# Main-v4_0.net
KiCad netlist of a schematic drawn in EAGLE
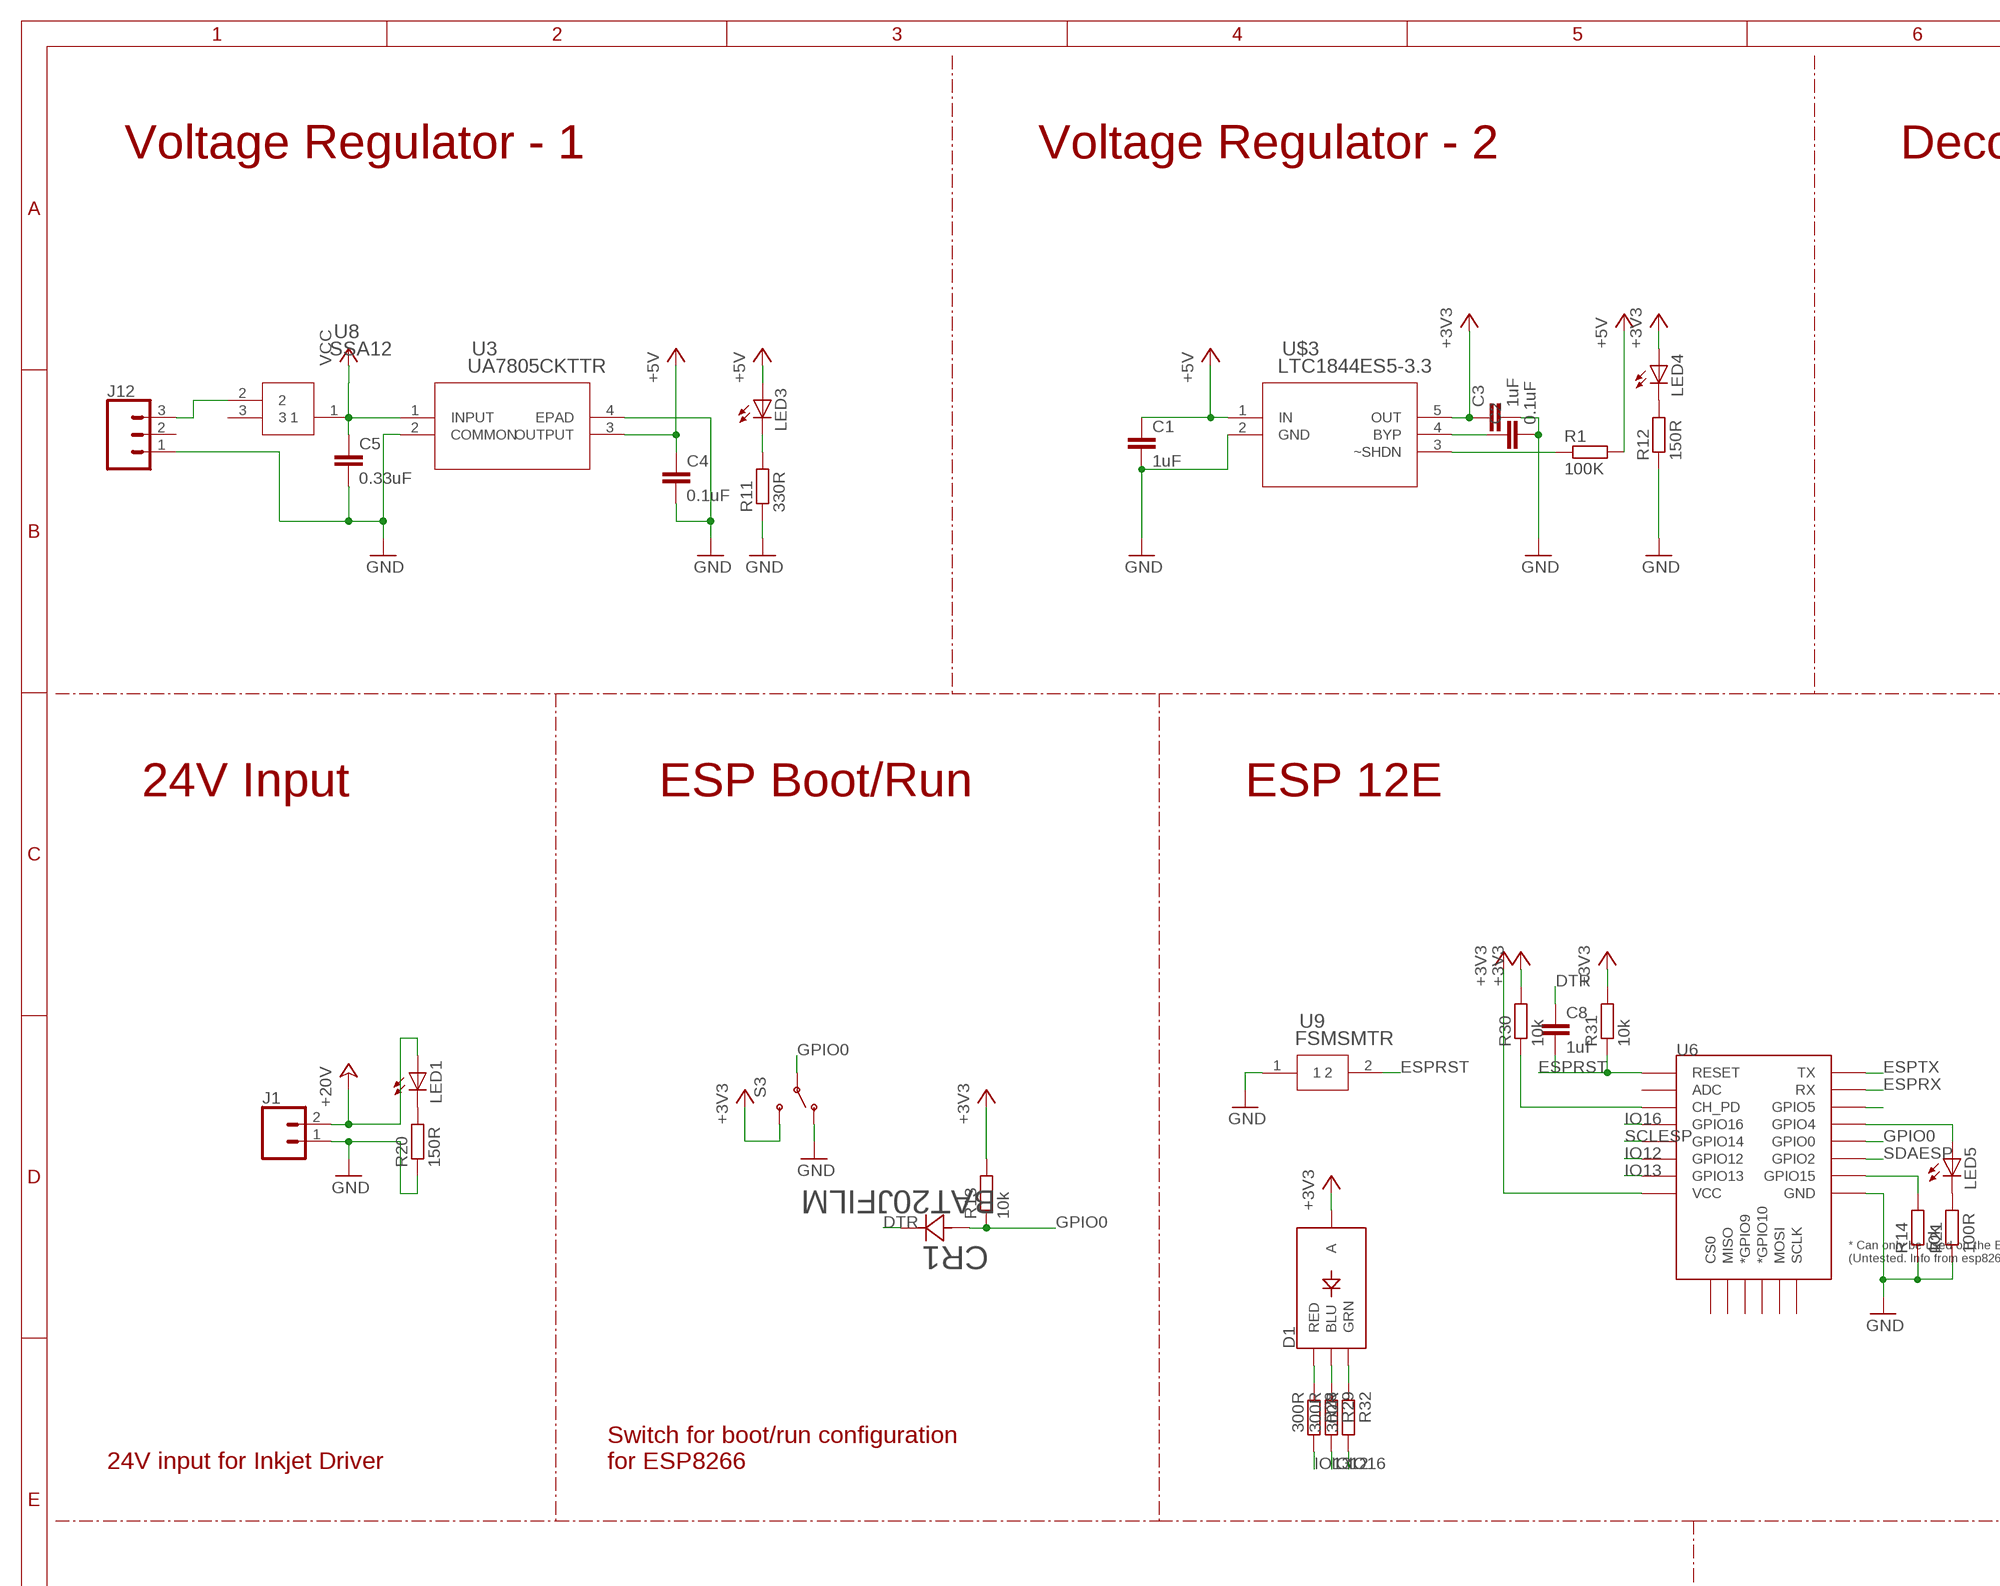
[diagram p0: schematic, sheet 1, part 1 of 3]
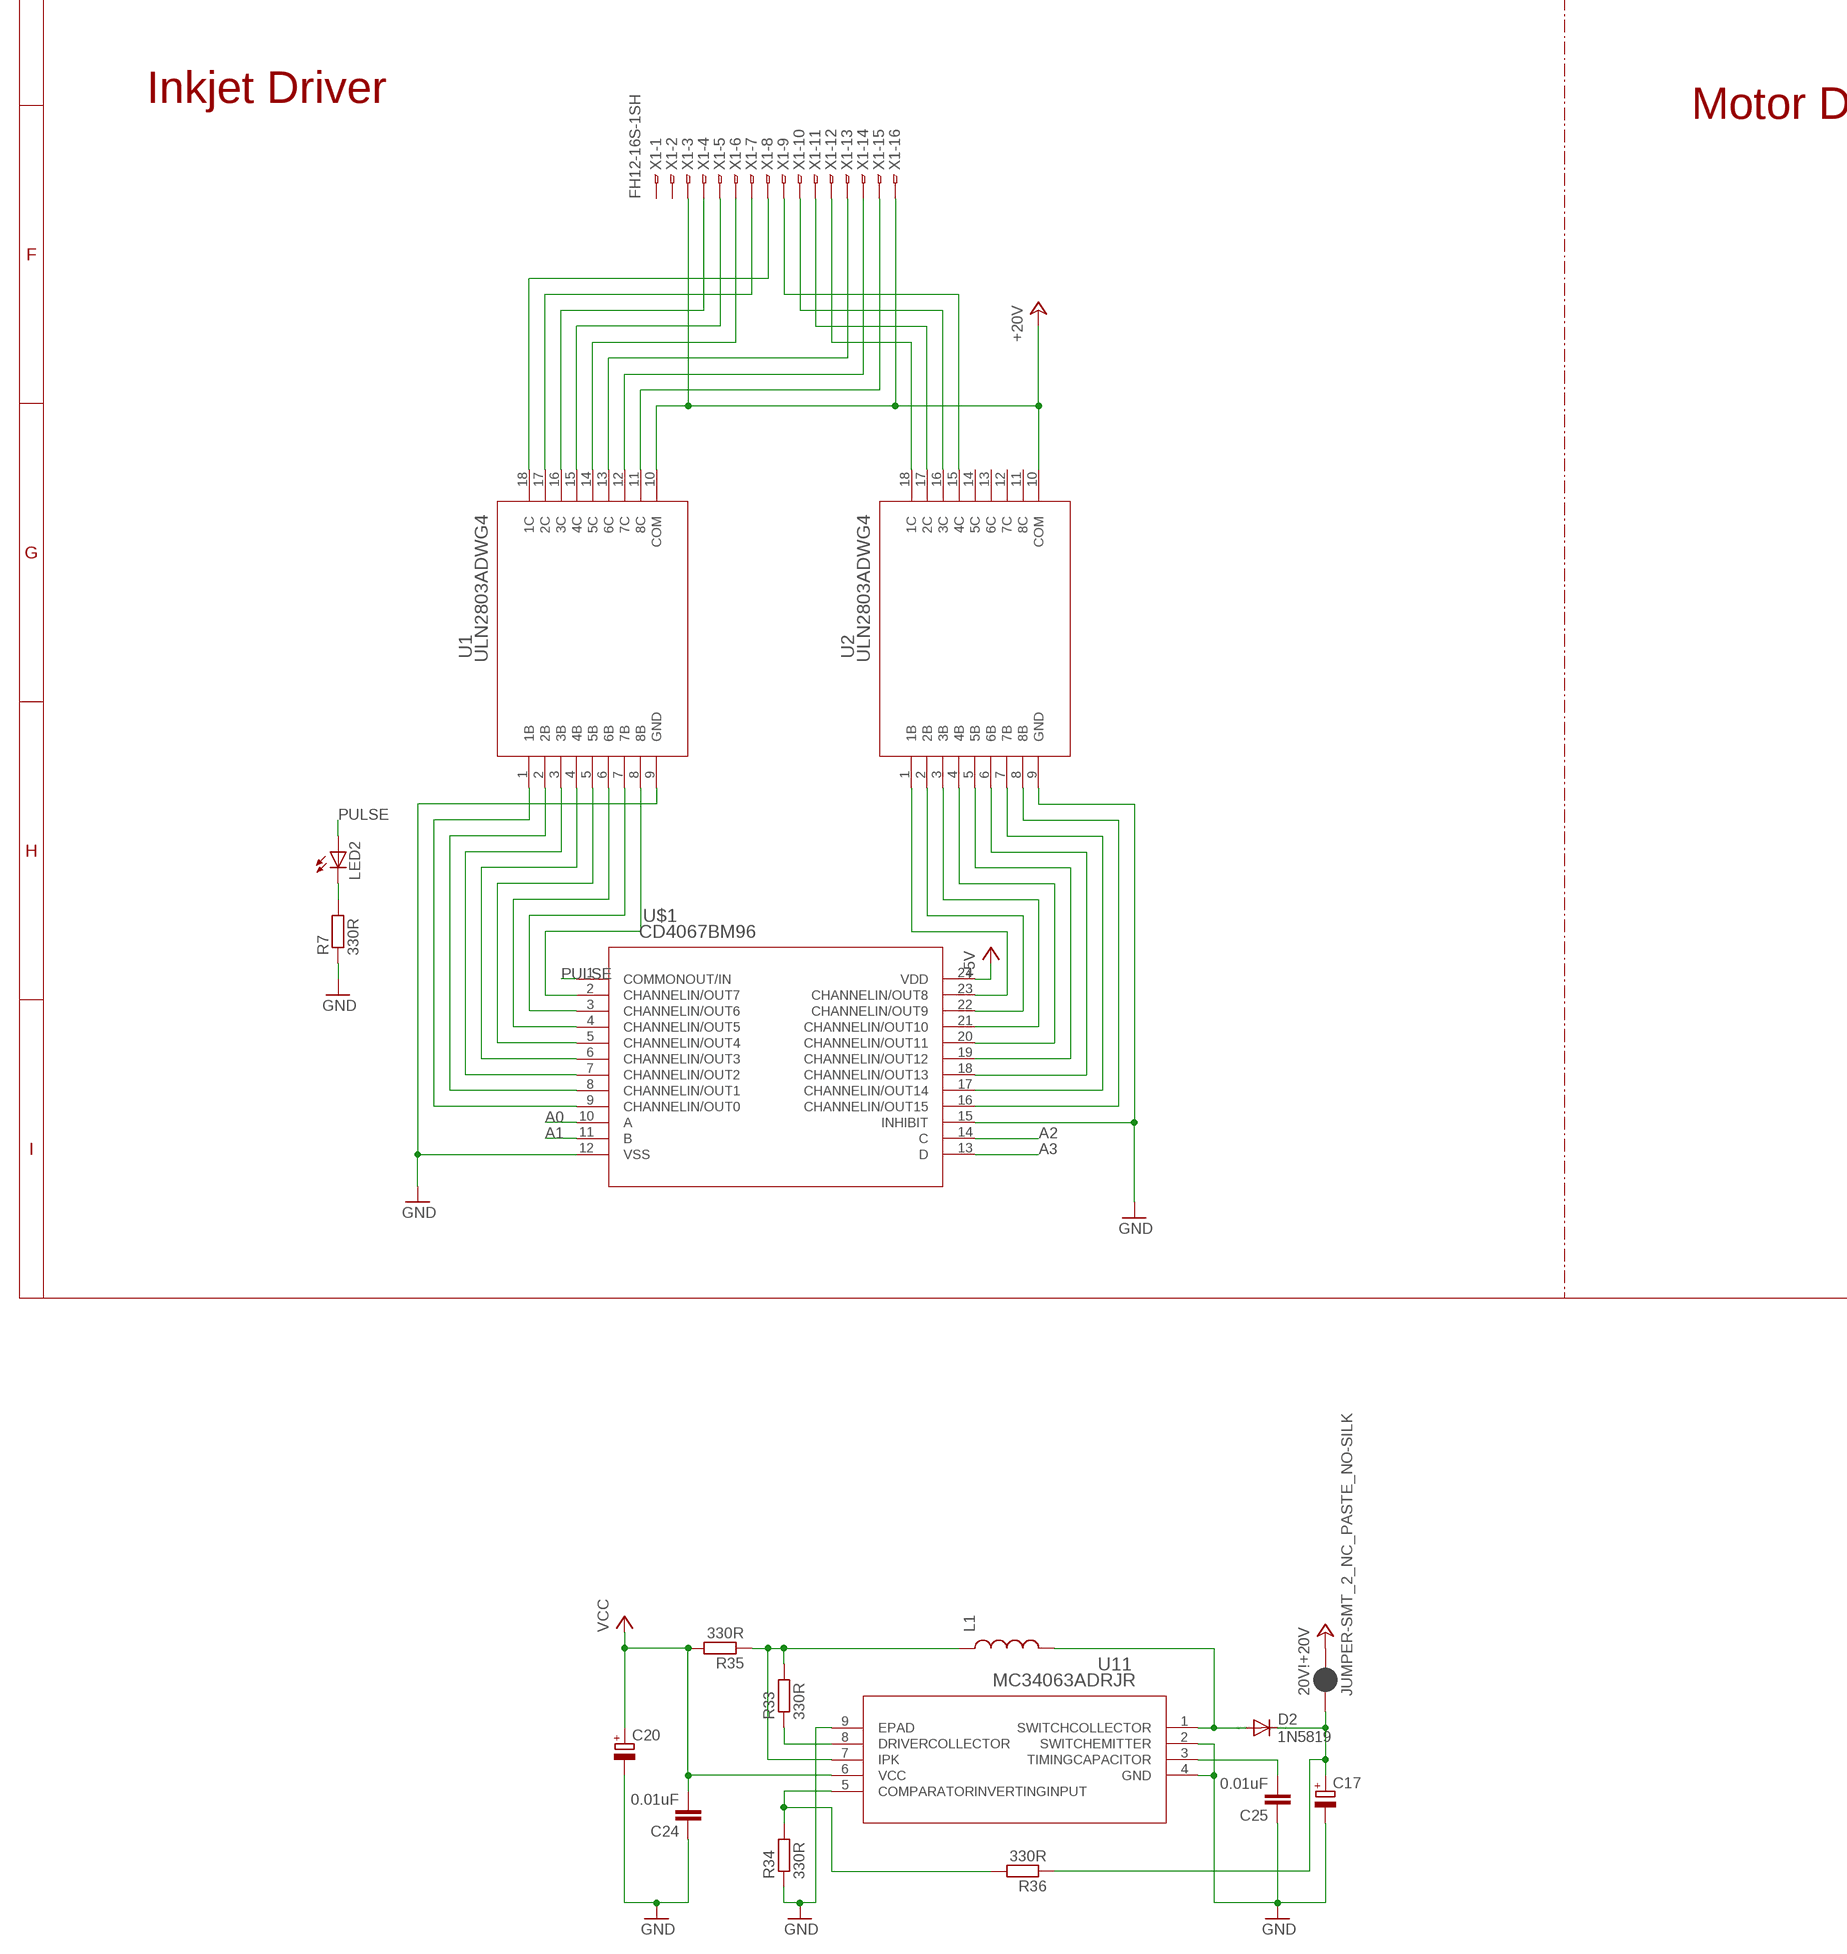
[diagram p1: schematic, sheet 1, part 2 of 3]
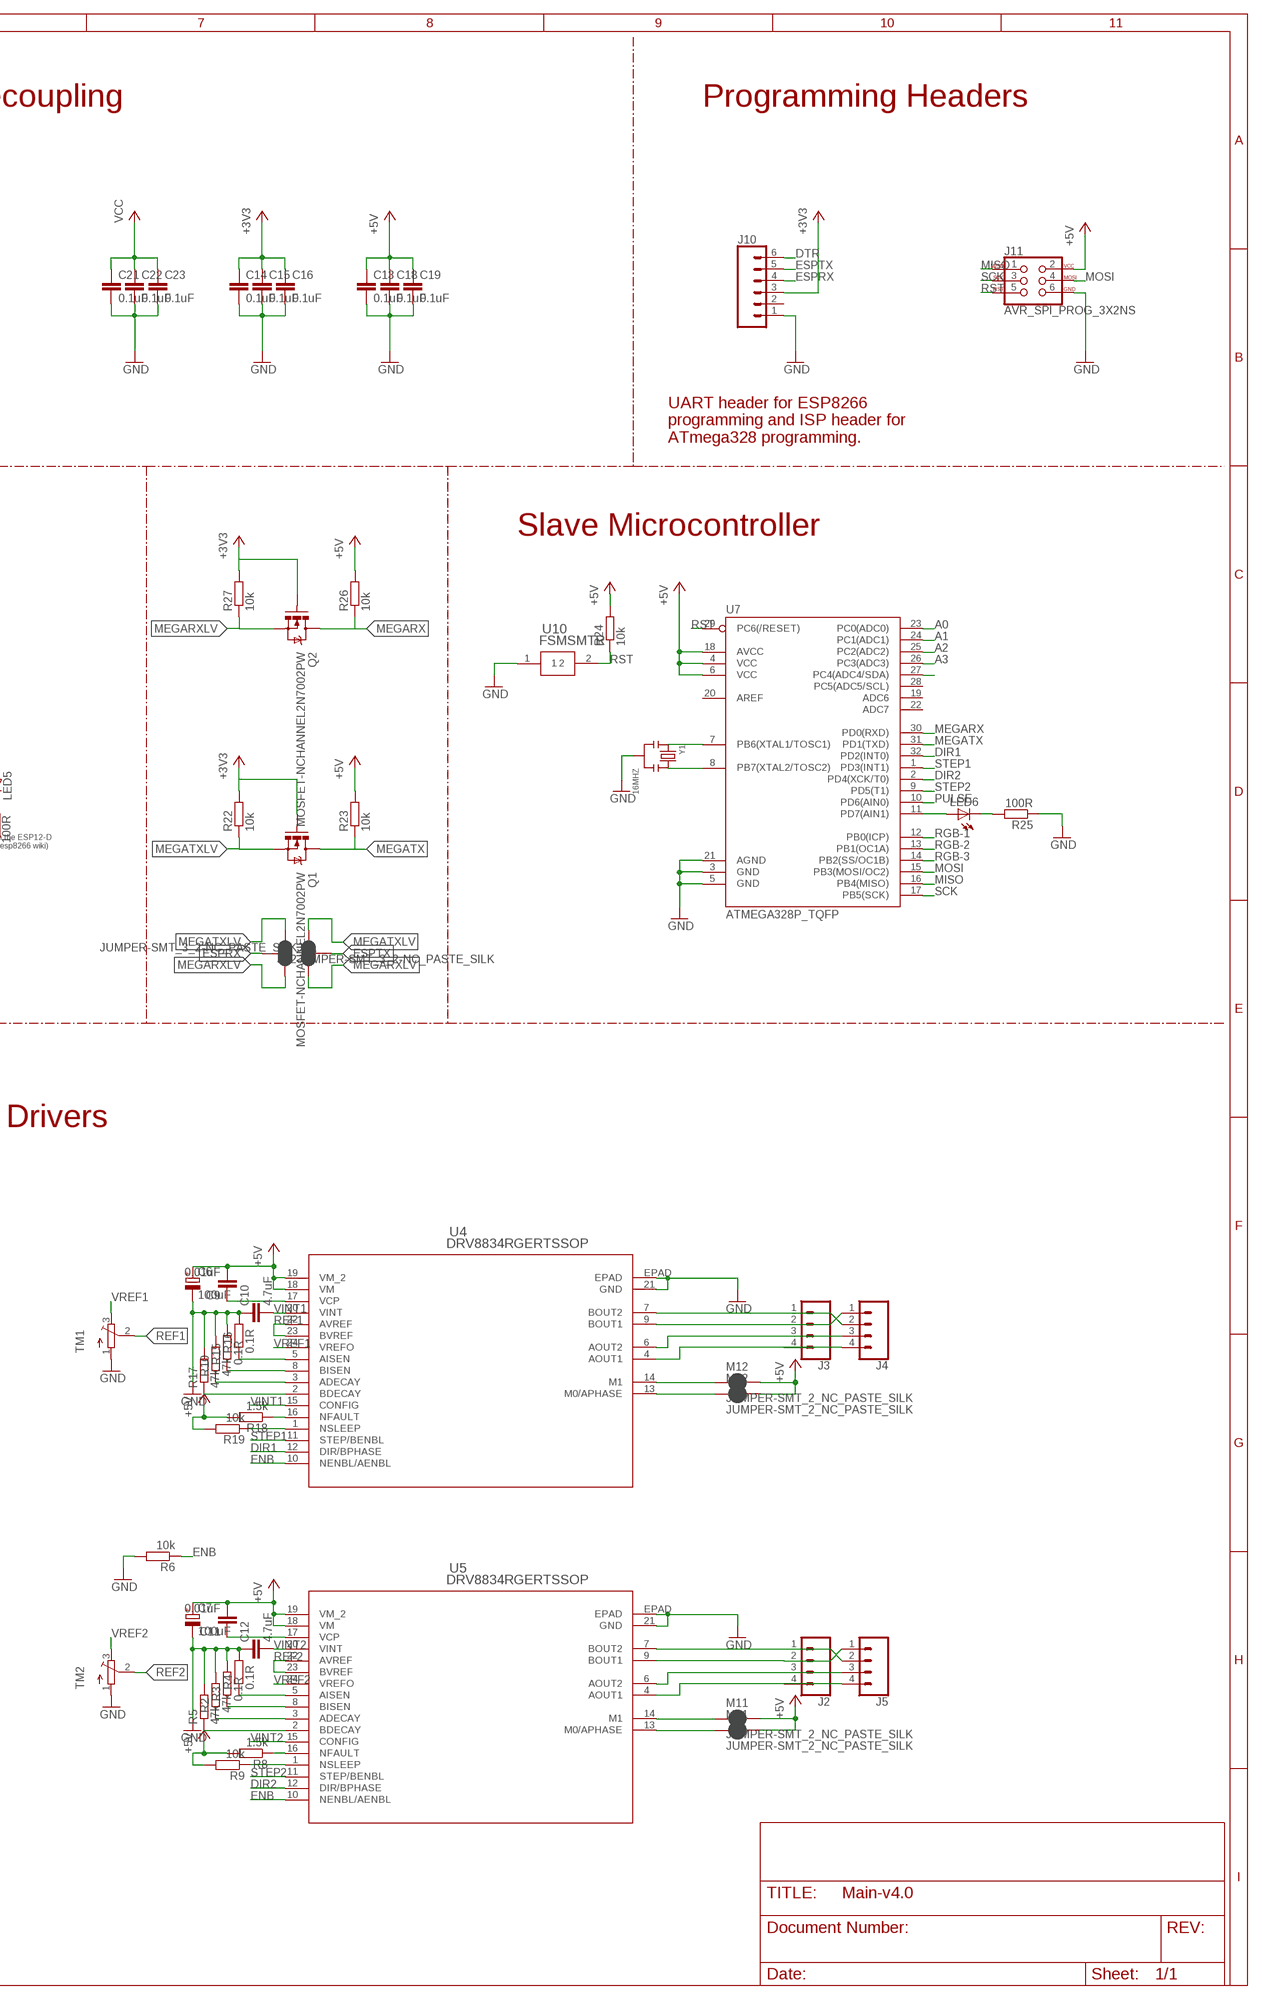
[diagram p2: schematic, sheet 1, part 3 of 3]

(export (version "E")
  (design (tool "Eeschema 10.0.6"))
  (components
    (comp (ref "20V!")
      (value "JUMPER-SMT_2_NC_PASTE_NO-SILK")
      (footprint "eagle-import:SMT-JUMPER_2_NC_PASTE_NO-SILK")
      (libsource (lib "eagle-import") (part "JUMPER-SMT_2_NC_PASTE_NO-SILK"))
    )
    (comp (ref "C1")
      (value "1uF")
      (footprint "eagle-import:C0603")
      (libsource (lib "eagle-import") (part "C-EUC0603"))
    )
    (comp (ref "C2")
      (value "0.1uF")
      (footprint "eagle-import:C0603")
      (libsource (lib "eagle-import") (part "C-EUC0603"))
    )
    (comp (ref "C3")
      (value "1uF")
      (footprint "eagle-import:C0603")
      (libsource (lib "eagle-import") (part "C-EUC0603"))
    )
    (comp (ref "C4")
      (value "0.1uF")
      (footprint "eagle-import:C0603")
      (libsource (lib "eagle-import") (part "C-EUC0603"))
    )
    (comp (ref "C5")
      (value "0.33uF")
      (footprint "eagle-import:C0603")
      (libsource (lib "eagle-import") (part "C-EUC0603"))
    )
    (comp (ref "C6")
      (value "100uF")
      (footprint "eagle-import:E5-5")
      (libsource (lib "eagle-import") (part "CPOL-EUE5-5"))
    )
    (comp (ref "C7")
      (value "100uF")
      (footprint "eagle-import:E5-5")
      (libsource (lib "eagle-import") (part "CPOL-EUE5-5"))
    )
    (comp (ref "C8")
      (value "1uf")
      (footprint "eagle-import:C0603")
      (libsource (lib "eagle-import") (part "resistor_348_C-EUC0603"))
    )
    (comp (ref "C9")
      (value "0.01uF")
      (footprint "eagle-import:C0603K")
      (libsource (lib "eagle-import") (part "resistor_348_C-EUC0603K"))
    )
    (comp (ref "C10")
      (value "4.7uF")
      (footprint "eagle-import:C0603K")
      (libsource (lib "eagle-import") (part "resistor_348_C-EUC0603K"))
    )
    (comp (ref "C11")
      (value "0.01uF")
      (footprint "eagle-import:C0603K")
      (libsource (lib "eagle-import") (part "resistor_348_C-EUC0603K"))
    )
    (comp (ref "C12")
      (value "4.7uF")
      (footprint "eagle-import:C0603K")
      (libsource (lib "eagle-import") (part "resistor_348_C-EUC0603K"))
    )
    (comp (ref "C13")
      (value "0.1uF")
      (footprint "eagle-import:C0603")
      (libsource (lib "eagle-import") (part "C-EUC0603"))
    )
    (comp (ref "C14")
      (value "0.1uF")
      (footprint "eagle-import:C0603")
      (libsource (lib "eagle-import") (part "C-EUC0603"))
    )
    (comp (ref "C15")
      (value "0.1uF")
      (footprint "eagle-import:C0603")
      (libsource (lib "eagle-import") (part "C-EUC0603"))
    )
    (comp (ref "C16")
      (value "0.1uF")
      (footprint "eagle-import:C0603")
      (libsource (lib "eagle-import") (part "C-EUC0603"))
    )
    (comp (ref "C17")
      (value "CPOL-EU153CLV-1010")
      (footprint "eagle-import:153CLV-1010")
      (libsource (lib "eagle-import") (part "resistor_348_CPOL-EU153CLV-1010"))
    )
    (comp (ref "C18")
      (value "0.1uF")
      (footprint "eagle-import:C0603")
      (libsource (lib "eagle-import") (part "C-EUC0603"))
    )
    (comp (ref "C19")
      (value "0.1uF")
      (footprint "eagle-import:C0603")
      (libsource (lib "eagle-import") (part "C-EUC0603"))
    )
    (comp (ref "C20")
      (value "CPOL-EUSMCC")
      (footprint "eagle-import:SMC_C")
      (libsource (lib "eagle-import") (part "resistor_348_CPOL-EUSMCC"))
    )
    (comp (ref "C21")
      (value "0.1uF")
      (footprint "eagle-import:C0603")
      (libsource (lib "eagle-import") (part "C-EUC0603"))
    )
    (comp (ref "C22")
      (value "0.1uF")
      (footprint "eagle-import:C0603")
      (libsource (lib "eagle-import") (part "C-EUC0603"))
    )
    (comp (ref "C23")
      (value "0.1uF")
      (footprint "eagle-import:C0603")
      (libsource (lib "eagle-import") (part "C-EUC0603"))
    )
    (comp (ref "C24")
      (value "0.01uF")
      (footprint "eagle-import:C0603K")
      (libsource (lib "eagle-import") (part "resistor_348_C-EUC0603K"))
    )
    (comp (ref "C25")
      (value "0.01uF")
      (footprint "eagle-import:C0603K")
      (libsource (lib "eagle-import") (part "resistor_348_C-EUC0603K"))
    )
    (comp (ref "CR1")
      (value "BAT20JFILM")
      (footprint "eagle-import:SOD-323")
      (libsource (lib "eagle-import") (part "BAT20JFILM"))
    )
    (comp (ref "D1")
      (value "LED-RGB-CASMD")
      (footprint "eagle-import:LED-TRICOLOR-SMD")
      (libsource (lib "eagle-import") (part "LED-RGB-CASMD"))
    )
    (comp (ref "D2")
      (value "1N5819")
      (footprint "eagle-import:SOD123")
      (libsource (lib "eagle-import") (part "1N5819"))
    )
    (comp (ref "J1")
      (value "CONN_02")
      (footprint "eagle-import:1X02")
      (libsource (lib "eagle-import") (part "CONN_02"))
    )
    (comp (ref "J2")
      (value "CONN_04")
      (footprint "eagle-import:1X04")
      (libsource (lib "eagle-import") (part "CONN_04"))
    )
    (comp (ref "J3")
      (value "CONN_04")
      (footprint "eagle-import:1X04")
      (libsource (lib "eagle-import") (part "CONN_04"))
    )
    (comp (ref "J4")
      (value "CONN_04")
      (footprint "eagle-import:1X04")
      (libsource (lib "eagle-import") (part "CONN_04"))
    )
    (comp (ref "J5")
      (value "CONN_04")
      (footprint "eagle-import:1X04")
      (libsource (lib "eagle-import") (part "CONN_04"))
    )
    (comp (ref "J10")
      (value "CONN_06NO_SILK_NO_POP")
      (footprint "eagle-import:1X06_NO_SILK")
      (libsource (lib "eagle-import") (part "CONN_06NO_SILK_NO_POP"))
    )
    (comp (ref "J11")
      (value "AVR_SPI_PROG_3X2NS")
      (footprint "eagle-import:2X3-NS")
      (libsource (lib "eagle-import") (part "AVR_SPI_PROG_3X2NS"))
    )
    (comp (ref "J12")
      (value "CONN_03")
      (footprint "eagle-import:1X03")
      (libsource (lib "eagle-import") (part "CONN_03"))
    )
    (comp (ref "JP1")
      (value "JUMPER-SMT_3_2-NC_PASTE_SILK")
      (footprint "eagle-import:SMT-JUMPER_3_2-NC_PASTE_SILK")
      (libsource (lib "eagle-import") (part "JUMPER-SMT_3_2-NC_PASTE_SILK"))
    )
    (comp (ref "JP2")
      (value "JUMPER-SMT_3_2-NC_PASTE_SILK")
      (footprint "eagle-import:SMT-JUMPER_3_2-NC_PASTE_SILK")
      (libsource (lib "eagle-import") (part "JUMPER-SMT_3_2-NC_PASTE_SILK"))
    )
    (comp (ref "L1")
      (value "INDUCTORCR54")
      (footprint "eagle-import:CR54")
      (libsource (lib "eagle-import") (part "INDUCTORCR54"))
    )
    (comp (ref "LED1")
      (value "LEDSML0603")
      (footprint "eagle-import:SML0603")
      (libsource (lib "eagle-import") (part "LEDSML0603"))
    )
    (comp (ref "LED2")
      (value "LEDSML0603")
      (footprint "eagle-import:SML0603")
      (libsource (lib "eagle-import") (part "LEDSML0603"))
    )
    (comp (ref "LED3")
      (value "LEDSML0603")
      (footprint "eagle-import:SML0603")
      (libsource (lib "eagle-import") (part "LEDSML0603"))
    )
    (comp (ref "LED4")
      (value "LEDSML0603")
      (footprint "eagle-import:SML0603")
      (libsource (lib "eagle-import") (part "LEDSML0603"))
    )
    (comp (ref "LED5")
      (value "LEDSML0603")
      (footprint "eagle-import:SML0603")
      (libsource (lib "eagle-import") (part "LEDSML0603"))
    )
    (comp (ref "LED6")
      (value "LEDSML0603")
      (footprint "eagle-import:SML0603")
      (libsource (lib "eagle-import") (part "LEDSML0603"))
    )
    (comp (ref "M01")
      (value "JUMPER-SMT_2_NC_PASTE_SILK")
      (footprint "eagle-import:SMT-JUMPER_2_NC_PASTE_SILK")
      (libsource (lib "eagle-import") (part "JUMPER-SMT_2_NC_PASTE_SILK"))
    )
    (comp (ref "M02")
      (value "JUMPER-SMT_2_NC_PASTE_SILK")
      (footprint "eagle-import:SMT-JUMPER_2_NC_PASTE_SILK")
      (libsource (lib "eagle-import") (part "JUMPER-SMT_2_NC_PASTE_SILK"))
    )
    (comp (ref "M11")
      (value "JUMPER-SMT_2_NC_PASTE_SILK")
      (footprint "eagle-import:SMT-JUMPER_2_NC_PASTE_SILK")
      (libsource (lib "eagle-import") (part "JUMPER-SMT_2_NC_PASTE_SILK"))
    )
    (comp (ref "M12")
      (value "JUMPER-SMT_2_NC_PASTE_SILK")
      (footprint "eagle-import:SMT-JUMPER_2_NC_PASTE_SILK")
      (libsource (lib "eagle-import") (part "JUMPER-SMT_2_NC_PASTE_SILK"))
    )
    (comp (ref "Q1")
      (value "MOSFET-NCHANNEL2N7002PW")
      (footprint "eagle-import:SOT323")
      (libsource (lib "eagle-import") (part "MOSFET-NCHANNEL2N7002PW"))
    )
    (comp (ref "Q2")
      (value "MOSFET-NCHANNEL2N7002PW")
      (footprint "eagle-import:SOT323")
      (libsource (lib "eagle-import") (part "MOSFET-NCHANNEL2N7002PW"))
    )
    (comp (ref "R1")
      (value "100K")
      (footprint "eagle-import:R0603")
      (libsource (lib "eagle-import") (part "R-EU_R0603"))
    )
    (comp (ref "R2")
      (value "47k")
      (footprint "eagle-import:R0402")
      (libsource (lib "eagle-import") (part "resistor_348_R-EU_R0402"))
    )
    (comp (ref "R3")
      (value "0.1R")
      (footprint "eagle-import:R0402")
      (libsource (lib "eagle-import") (part "resistor_348_R-EU_R0402"))
    )
    (comp (ref "R4")
      (value "0.1R")
      (footprint "eagle-import:R0402")
      (libsource (lib "eagle-import") (part "resistor_348_R-EU_R0402"))
    )
    (comp (ref "R5")
      (value "47k")
      (footprint "eagle-import:R0402")
      (libsource (lib "eagle-import") (part "resistor_348_R-EU_R0402"))
    )
    (comp (ref "R6")
      (value "10k")
      (footprint "eagle-import:R0402")
      (libsource (lib "eagle-import") (part "resistor_348_R-EU_R0402"))
    )
    (comp (ref "R7")
      (value "330R")
      (footprint "eagle-import:R0603")
      (libsource (lib "eagle-import") (part "R-EU_R0603"))
    )
    (comp (ref "R8")
      (value "1.5k")
      (footprint "eagle-import:R0402")
      (libsource (lib "eagle-import") (part "resistor_348_R-EU_R0402"))
    )
    (comp (ref "R9")
      (value "10k")
      (footprint "eagle-import:R0402")
      (libsource (lib "eagle-import") (part "resistor_348_R-EU_R0402"))
    )
    (comp (ref "R10")
      (value "47k")
      (footprint "eagle-import:R0402")
      (libsource (lib "eagle-import") (part "resistor_348_R-EU_R0402"))
    )
    (comp (ref "R11")
      (value "330R")
      (footprint "eagle-import:R0603")
      (libsource (lib "eagle-import") (part "R-EU_R0603"))
    )
    (comp (ref "R12")
      (value "150R")
      (footprint "eagle-import:R0603")
      (libsource (lib "eagle-import") (part "R-EU_R0603"))
    )
    (comp (ref "R13")
      (value "10k")
      (footprint "eagle-import:R0603")
      (libsource (lib "eagle-import") (part "R-EU_R0603"))
    )
    (comp (ref "R14")
      (value "10k")
      (footprint "eagle-import:R0603")
      (libsource (lib "eagle-import") (part "R-EU_R0603"))
    )
    (comp (ref "R15")
      (value "0.1R")
      (footprint "eagle-import:R0402")
      (libsource (lib "eagle-import") (part "resistor_348_R-EU_R0402"))
    )
    (comp (ref "R16")
      (value "0.1R")
      (footprint "eagle-import:R0402")
      (libsource (lib "eagle-import") (part "resistor_348_R-EU_R0402"))
    )
    (comp (ref "R17")
      (value "47k")
      (footprint "eagle-import:R0402")
      (libsource (lib "eagle-import") (part "resistor_348_R-EU_R0402"))
    )
    (comp (ref "R18")
      (value "1.5k")
      (footprint "eagle-import:R0402")
      (libsource (lib "eagle-import") (part "resistor_348_R-EU_R0402"))
    )
    (comp (ref "R19")
      (value "10k")
      (footprint "eagle-import:R0402")
      (libsource (lib "eagle-import") (part "resistor_348_R-EU_R0402"))
    )
    (comp (ref "R20")
      (value "150R")
      (footprint "eagle-import:R0603")
      (libsource (lib "eagle-import") (part "R-EU_R0603"))
    )
    (comp (ref "R21")
      (value "100R")
      (footprint "eagle-import:R0603")
      (libsource (lib "eagle-import") (part "R-EU_R0603"))
    )
    (comp (ref "R22")
      (value "10k")
      (footprint "eagle-import:R0603")
      (libsource (lib "eagle-import") (part "R-EU_R0603"))
    )
    (comp (ref "R23")
      (value "10k")
      (footprint "eagle-import:R0603")
      (libsource (lib "eagle-import") (part "R-EU_R0603"))
    )
    (comp (ref "R24")
      (value "10k")
      (footprint "eagle-import:R0603")
      (libsource (lib "eagle-import") (part "R-EU_R0603"))
    )
    (comp (ref "R25")
      (value "100R")
      (footprint "eagle-import:R0603")
      (libsource (lib "eagle-import") (part "R-EU_R0603"))
    )
    (comp (ref "R26")
      (value "10k")
      (footprint "eagle-import:R0603")
      (libsource (lib "eagle-import") (part "R-EU_R0603"))
    )
    (comp (ref "R27")
      (value "10k")
      (footprint "eagle-import:R0603")
      (libsource (lib "eagle-import") (part "R-EU_R0603"))
    )
    (comp (ref "R28")
      (value "300R")
      (footprint "eagle-import:R0603")
      (libsource (lib "eagle-import") (part "R-EU_R0603"))
    )
    (comp (ref "R29")
      (value "300R")
      (footprint "eagle-import:R0603")
      (libsource (lib "eagle-import") (part "R-EU_R0603"))
    )
    (comp (ref "R30")
      (value "10k")
      (footprint "eagle-import:R0603")
      (libsource (lib "eagle-import") (part "R-EU_R0603"))
    )
    (comp (ref "R31")
      (value "10k")
      (footprint "eagle-import:R0603")
      (libsource (lib "eagle-import") (part "R-EU_R0603"))
    )
    (comp (ref "R32")
      (value "300R")
      (footprint "eagle-import:R0603")
      (libsource (lib "eagle-import") (part "R-EU_R0603"))
    )
    (comp (ref "R33")
      (value "330R")
      (footprint "eagle-import:R0603")
      (libsource (lib "eagle-import") (part "R-EU_R0603"))
    )
    (comp (ref "R34")
      (value "330R")
      (footprint "eagle-import:R0603")
      (libsource (lib "eagle-import") (part "R-EU_R0603"))
    )
    (comp (ref "R35")
      (value "330R")
      (footprint "eagle-import:R0603")
      (libsource (lib "eagle-import") (part "R-EU_R0603"))
    )
    (comp (ref "R36")
      (value "330R")
      (footprint "eagle-import:R0603")
      (libsource (lib "eagle-import") (part "R-EU_R0603"))
    )
    (comp (ref "S3")
      (value "SWITCH-SPDT-SMD-A")
      (footprint "eagle-import:SWITCH-SPST-SMD-A")
      (libsource (lib "eagle-import") (part "SWITCH-SPDT-SMD-A"))
    )
    (comp (ref "TM1")
      (value "TRIMPOTTC33X")
      (footprint "eagle-import:TC33X")
      (libsource (lib "eagle-import") (part "TRIMPOTTC33X"))
    )
    (comp (ref "TM2")
      (value "TRIMPOTTC33X")
      (footprint "eagle-import:TC33X")
      (libsource (lib "eagle-import") (part "TRIMPOTTC33X"))
    )
    (comp (ref "U$1")
      (value "CD4067BM96")
      (footprint "eagle-import:DW24")
      (fields (field (name "MANUFACTURER_PART_NUMBER") "CD4067B_DW_24"))
      (libsource (lib "eagle-import") (part "CD4067BM96"))
    )
    (comp (ref "U$3")
      (value "LTC1844ES5-3.3")
      (footprint "eagle-import:TSOT-23_S5")
      (libsource (lib "eagle-import") (part "LTC1844ES5-3.3"))
    )
    (comp (ref "U1")
      (value "ULN2803ADWG4")
      (footprint "eagle-import:DW18")
      (libsource (lib "eagle-import") (part "ULN2803ADWG4"))
    )
    (comp (ref "U2")
      (value "ULN2803ADWG4")
      (footprint "eagle-import:DW18")
      (libsource (lib "eagle-import") (part "ULN2803ADWG4"))
    )
    (comp (ref "U3")
      (value "UA7805CKTTR")
      (footprint "eagle-import:KTT3_6P22X6P6")
      (libsource (lib "eagle-import") (part "UA7805CKTTR"))
    )
    (comp (ref "U4")
      (value "DRV8834RGERTSSOP")
      (footprint "eagle-import:PWP_24")
      (libsource (lib "eagle-import") (part "DRV8834RGERTSSOP"))
    )
    (comp (ref "U5")
      (value "DRV8834RGERTSSOP")
      (footprint "eagle-import:PWP_24")
      (libsource (lib "eagle-import") (part "DRV8834RGERTSSOP"))
    )
    (comp (ref "U6")
      (value "ESP12ESMD")
      (footprint "eagle-import:ESP12E-SMD")
      (libsource (lib "eagle-import") (part "ESP12ESMD"))
    )
    (comp (ref "U7")
      (value "ATMEGA328P_TQFP")
      (footprint "eagle-import:TQFP32-08")
      (libsource (lib "eagle-import") (part "ATMEGA328P_TQFP"))
    )
    (comp (ref "U8")
      (value "SSA12")
      (footprint "eagle-import:SWSIP3-P98")
      (libsource (lib "eagle-import") (part "SSA12"))
    )
    (comp (ref "U9")
      (value "FSMSMTR")
      (footprint "eagle-import:SWITCH_FSMSMTR")
      (libsource (lib "eagle-import") (part "FSMSMTR"))
    )
    (comp (ref "U10")
      (value "FSMSMTR")
      (footprint "eagle-import:SWITCH_FSMSMTR")
      (libsource (lib "eagle-import") (part "FSMSMTR"))
    )
    (comp (ref "U11")
      (value "MC34063ADRJR")
      (footprint "eagle-import:DRJ8_2P2X3")
      (libsource (lib "eagle-import") (part "MC34063ADRJR"))
    )
    (comp (ref "X1")
      (value "FH12-16S-1SH")
      (footprint "eagle-import:FH12-16S-1SH")
      (libsource (lib "eagle-import") (part "FH12-16S-1SH"))
    )
    (comp (ref "Y1")
      (value "16MHZ")
      (footprint "eagle-import:X3-SMD-3.6X1.3X0.8MM")
      (fields (field (name "MPN") "CSTCE16M0V53-R0"))
      (libsource (lib "eagle-import") (part "SMD-RESONATOR-16MHZ-15PF-0.5%-40R(3P-3.2X1.3MM)"))
    )
  )
  (nets
    (net (code "1") (name "+3V3") (class "Default")
      (node (ref "C14") (pin "1") (pinfunction "1_1") (pintype "passive"))
      (node (ref "C15") (pin "1") (pinfunction "1_1") (pintype "passive"))
      (node (ref "C16") (pin "1") (pinfunction "1_1") (pintype "passive"))
      (node (ref "C3") (pin "1") (pinfunction "1_1") (pintype "passive"))
      (node (ref "D1") (pin "A") (pinfunction "A_A") (pintype "bidirectional"))
      (node (ref "J10") (pin "3") (pinfunction "3_3") (pintype "passive"))
      (node (ref "LED4") (pin "A") (pinfunction "A_A") (pintype "passive"))
      (node (ref "Q1") (pin "1") (pinfunction "G_1") (pintype "passive"))
      (node (ref "Q2") (pin "1") (pinfunction "G_1") (pintype "passive"))
      (node (ref "R13") (pin "2") (pinfunction "2_2") (pintype "passive"))
      (node (ref "R22") (pin "2") (pinfunction "2_2") (pintype "passive"))
      (node (ref "R27") (pin "2") (pinfunction "2_2") (pintype "passive"))
      (node (ref "R30") (pin "2") (pinfunction "2_2") (pintype "passive"))
      (node (ref "R31") (pin "2") (pinfunction "2_2") (pintype "passive"))
      (node (ref "S3") (pin "3") (pinfunction "S_3") (pintype "passive"))
      (node (ref "U$3") (pin "5") (pinfunction "OUT_5") (pintype "passive"))
      (node (ref "U6") (pin "VCC") (pinfunction "VCC_VCC") (pintype "bidirectional"))
    )
    (net (code "2") (name "+5V") (class "Default")
      (node (ref "C1") (pin "1") (pinfunction "1_1") (pintype "passive"))
      (node (ref "C11") (pin "2") (pinfunction "2_2") (pintype "passive"))
      (node (ref "C13") (pin "1") (pinfunction "1_1") (pintype "passive"))
      (node (ref "C18") (pin "1") (pinfunction "1_1") (pintype "passive"))
      (node (ref "C19") (pin "1") (pinfunction "1_1") (pintype "passive"))
      (node (ref "C4") (pin "1") (pinfunction "1_1") (pintype "passive"))
      (node (ref "C6") (pin "+") (pinfunction "+_+") (pintype "passive"))
      (node (ref "C7") (pin "+") (pinfunction "+_+") (pintype "passive"))
      (node (ref "C9") (pin "2") (pinfunction "2_2") (pintype "passive"))
      (node (ref "J11") (pin "2") (pinfunction "2_2") (pintype "passive"))
      (node (ref "LED3") (pin "A") (pinfunction "A_A") (pintype "passive"))
      (node (ref "M01") (pin "2") (pinfunction "2_2") (pintype "passive"))
      (node (ref "M02") (pin "2") (pinfunction "2_2") (pintype "passive"))
      (node (ref "M11") (pin "2") (pinfunction "2_2") (pintype "passive"))
      (node (ref "M12") (pin "2") (pinfunction "2_2") (pintype "passive"))
      (node (ref "R1") (pin "2") (pinfunction "2_2") (pintype "passive"))
      (node (ref "R18") (pin "2") (pinfunction "2_2") (pintype "passive"))
      (node (ref "R19") (pin "2") (pinfunction "2_2") (pintype "passive"))
      (node (ref "R23") (pin "2") (pinfunction "2_2") (pintype "passive"))
      (node (ref "R24") (pin "2") (pinfunction "2_2") (pintype "passive"))
      (node (ref "R26") (pin "2") (pinfunction "2_2") (pintype "passive"))
      (node (ref "R8") (pin "2") (pinfunction "2_2") (pintype "passive"))
      (node (ref "R9") (pin "2") (pinfunction "2_2") (pintype "passive"))
      (node (ref "U$1") (pin "24") (pinfunction "VDD_24") (pintype "power_in"))
      (node (ref "U$3") (pin "1") (pinfunction "IN_1") (pintype "passive"))
      (node (ref "U3") (pin "3") (pinfunction "OUTPUT_3") (pintype "output"))
      (node (ref "U4") (pin "18") (pinfunction "VM_18") (pintype "power_in"))
      (node (ref "U4") (pin "19") (pinfunction "VM_2_19") (pintype "power_in"))
      (node (ref "U5") (pin "18") (pinfunction "VM_18") (pintype "power_in"))
      (node (ref "U5") (pin "19") (pinfunction "VM_2_19") (pintype "power_in"))
      (node (ref "U7") (pin "18") (pinfunction "AVCC_18") (pintype "bidirectional"))
      (node (ref "U7") (pin "4") (pinfunction "VCC_4") (pintype "bidirectional"))
      (node (ref "U7") (pin "6") (pinfunction "VCC_6") (pintype "bidirectional"))
    )
    (net (code "3") (name "+20V") (class "Default")
      (node (ref "20V!") (pin "2") (pinfunction "2_2") (pintype "passive"))
      (node (ref "J1") (pin "2") (pinfunction "2_2") (pintype "passive"))
      (node (ref "LED1") (pin "A") (pinfunction "A_A") (pintype "passive"))
      (node (ref "U1") (pin "10") (pinfunction "COM_10") (pintype "passive"))
      (node (ref "U2") (pin "10") (pinfunction "COM_10") (pintype "passive"))
      (node (ref "X1") (pin "16") (pinfunction "1_16") (pintype "passive"))
      (node (ref "X1") (pin "3") (pinfunction "1_3") (pintype "passive"))
    )
    (net (code "4") (name "/A0") (class "Default")
      (node (ref "U$1") (pin "10") (pinfunction "A_10") (pintype "passive"))
      (node (ref "U7") (pin "23") (pinfunction "PC0(ADC0)_23") (pintype "bidirectional"))
    )
    (net (code "5") (name "/A1") (class "Default")
      (node (ref "U$1") (pin "11") (pinfunction "B_11") (pintype "passive"))
      (node (ref "U7") (pin "24") (pinfunction "PC1(ADC1)_24") (pintype "bidirectional"))
    )
    (net (code "6") (name "/A2") (class "Default")
      (node (ref "U$1") (pin "14") (pinfunction "C_14") (pintype "passive"))
      (node (ref "U7") (pin "25") (pinfunction "PC2(ADC2)_25") (pintype "bidirectional"))
    )
    (net (code "7") (name "/A3") (class "Default")
      (node (ref "U$1") (pin "13") (pinfunction "D_13") (pintype "passive"))
      (node (ref "U7") (pin "26") (pinfunction "PC3(ADC3)_26") (pintype "bidirectional"))
    )
    (net (code "8") (name "/DIR1") (class "Default")
      (node (ref "U4") (pin "12") (pinfunction "DIR/BPHASE_12") (pintype "input"))
      (node (ref "U7") (pin "32") (pinfunction "PD2(INT0)_32") (pintype "bidirectional"))
    )
    (net (code "9") (name "/DIR2") (class "Default")
      (node (ref "U5") (pin "12") (pinfunction "DIR/BPHASE_12") (pintype "input"))
      (node (ref "U7") (pin "2") (pinfunction "PD4(XCK/T0)_2") (pintype "bidirectional"))
    )
    (net (code "10") (name "/DTR") (class "Default")
      (node (ref "C8") (pin "1") (pinfunction "1_1") (pintype "passive"))
      (node (ref "CR1") (pin "1") (pinfunction "11_1") (pintype "passive"))
      (node (ref "J10") (pin "6") (pinfunction "6_6") (pintype "passive"))
    )
    (net (code "11") (name "/ENB") (class "Default")
      (node (ref "R6") (pin "1") (pinfunction "1_1") (pintype "passive"))
      (node (ref "U4") (pin "10") (pinfunction "NENBL/AENBL_10") (pintype "input"))
      (node (ref "U5") (pin "10") (pinfunction "NENBL/AENBL_10") (pintype "input"))
    )
    (net (code "12") (name "/ESPRST") (class "Default")
      (node (ref "C8") (pin "2") (pinfunction "2_2") (pintype "passive"))
      (node (ref "R31") (pin "1") (pinfunction "1_1") (pintype "passive"))
      (node (ref "U6") (pin "RESET") (pinfunction "RESET_RESET") (pintype "bidirectional"))
      (node (ref "U9") (pin "2") (pinfunction "2_2") (pintype "passive"))
    )
    (net (code "13") (name "/GPIO0") (class "Default")
      (node (ref "CR1") (pin "2") (pinfunction "22_2") (pintype "passive"))
      (node (ref "R13") (pin "1") (pinfunction "1_1") (pintype "passive"))
      (node (ref "S3") (pin "2") (pinfunction "P_2") (pintype "passive"))
      (node (ref "U6") (pin "GPIO0") (pinfunction "GPIO0_GPIO0") (pintype "bidirectional"))
    )
    (net (code "14") (name "/IO12") (class "Default")
      (node (ref "R29") (pin "2") (pinfunction "2_2") (pintype "passive"))
      (node (ref "U6") (pin "GPIO12") (pinfunction "GPIO12_GPIO12") (pintype "bidirectional"))
    )
    (net (code "15") (name "/IO13") (class "Default")
      (node (ref "R28") (pin "2") (pinfunction "2_2") (pintype "passive"))
      (node (ref "U6") (pin "GPIO13") (pinfunction "GPIO13_GPIO13") (pintype "bidirectional"))
    )
    (net (code "16") (name "/IO16") (class "Default")
      (node (ref "R32") (pin "2") (pinfunction "2_2") (pintype "passive"))
      (node (ref "U6") (pin "GPIO16") (pinfunction "GPIO16_GPIO16") (pintype "bidirectional"))
    )
    (net (code "17") (name "/MISO") (class "Default")
      (node (ref "J11") (pin "1") (pinfunction "1_1") (pintype "passive"))
      (node (ref "U7") (pin "16") (pinfunction "PB4(MISO)_16") (pintype "bidirectional"))
    )
    (net (code "18") (name "/MOSI") (class "Default")
      (node (ref "J11") (pin "4") (pinfunction "4_4") (pintype "passive"))
      (node (ref "U7") (pin "15") (pinfunction "PB3(MOSI/OC2)_15") (pintype "bidirectional"))
    )
    (net (code "19") (name "/PULSE") (class "Default")
      (node (ref "LED2") (pin "A") (pinfunction "A_A") (pintype "passive"))
      (node (ref "U$1") (pin "1") (pinfunction "COMMONOUT/IN_1") (pintype "bidirectional"))
      (node (ref "U7") (pin "10") (pinfunction "PD6(AIN0)_10") (pintype "bidirectional"))
    )
    (net (code "20") (name "/RGB-1") (class "Default")
      (node (ref "U7") (pin "12") (pinfunction "PB0(ICP)_12") (pintype "bidirectional"))
    )
    (net (code "21") (name "/RGB-2") (class "Default")
      (node (ref "U7") (pin "13") (pinfunction "PB1(OC1A)_13") (pintype "bidirectional"))
    )
    (net (code "22") (name "/RGB-3") (class "Default")
      (node (ref "U7") (pin "14") (pinfunction "PB2(SS/OC1B)_14") (pintype "bidirectional"))
    )
    (net (code "23") (name "/RST") (class "Default")
      (node (ref "J11") (pin "5") (pinfunction "5_5") (pintype "passive"))
      (node (ref "R24") (pin "1") (pinfunction "1_1") (pintype "passive"))
      (node (ref "U10") (pin "2") (pinfunction "2_2") (pintype "passive"))
      (node (ref "U7") (pin "29") (pinfunction "PC6(/RESET)_29") (pintype "bidirectional"))
    )
    (net (code "24") (name "/SCK") (class "Default")
      (node (ref "J11") (pin "3") (pinfunction "3_3") (pintype "passive"))
      (node (ref "U7") (pin "17") (pinfunction "PB5(SCK)_17") (pintype "bidirectional"))
    )
    (net (code "25") (name "/SCLESP") (class "Default")
      (node (ref "U6") (pin "GPIO14") (pinfunction "GPIO14_GPIO14") (pintype "bidirectional"))
    )
    (net (code "26") (name "/SDAESP") (class "Default")
      (node (ref "U6") (pin "GPIO2") (pinfunction "GPIO2_GPIO2") (pintype "bidirectional"))
    )
    (net (code "27") (name "/STEP1") (class "Default")
      (node (ref "U4") (pin "11") (pinfunction "STEP/BENBL_11") (pintype "input"))
      (node (ref "U7") (pin "1") (pinfunction "PD3(INT1)_1") (pintype "bidirectional"))
    )
    (net (code "28") (name "/STEP2") (class "Default")
      (node (ref "U5") (pin "11") (pinfunction "STEP/BENBL_11") (pintype "input"))
      (node (ref "U7") (pin "9") (pinfunction "PD5(T1)_9") (pintype "bidirectional"))
    )
    (net (code "29") (name "/VINT1") (class "Default")
      (node (ref "C10") (pin "2") (pinfunction "2_2") (pintype "passive"))
      (node (ref "U4") (pin "15") (pinfunction "CONFIG_15") (pintype "input"))
      (node (ref "U4") (pin "20") (pinfunction "VINT_20") (pintype "passive"))
    )
    (net (code "30") (name "/VINT2") (class "Default")
      (node (ref "C12") (pin "2") (pinfunction "2_2") (pintype "passive"))
      (node (ref "U5") (pin "15") (pinfunction "CONFIG_15") (pintype "input"))
      (node (ref "U5") (pin "20") (pinfunction "VINT_20") (pintype "passive"))
    )
    (net (code "31") (name "/VREF1") (class "Default")
      (node (ref "TM1") (pin "3") (pinfunction "E_3") (pintype "passive"))
      (node (ref "U4") (pin "24") (pinfunction "VREFO_24") (pintype "output"))
    )
    (net (code "32") (name "/VREF2") (class "Default")
      (node (ref "TM2") (pin "3") (pinfunction "E_3") (pintype "passive"))
      (node (ref "U5") (pin "24") (pinfunction "VREFO_24") (pintype "output"))
    )
    (net (code "33") (name "ESPRX") (class "Default")
      (node (ref "J10") (pin "4") (pinfunction "4_4") (pintype "passive"))
      (node (ref "JP1") (pin "2") (pinfunction "2_2") (pintype "passive"))
      (node (ref "U6") (pin "RXD0") (pinfunction "RX_RXD0") (pintype "bidirectional"))
    )
    (net (code "34") (name "ESPTX") (class "Default")
      (node (ref "J10") (pin "5") (pinfunction "5_5") (pintype "passive"))
      (node (ref "JP2") (pin "2") (pinfunction "2_2") (pintype "passive"))
      (node (ref "U6") (pin "TXD0") (pinfunction "TX_TXD0") (pintype "bidirectional"))
    )
    (net (code "35") (name "GND") (class "Default")
      (node (ref "C1") (pin "2") (pinfunction "2_2") (pintype "passive"))
      (node (ref "C10") (pin "1") (pinfunction "1_1") (pintype "passive"))
      (node (ref "C12") (pin "1") (pinfunction "1_1") (pintype "passive"))
      (node (ref "C13") (pin "2") (pinfunction "2_2") (pintype "passive"))
      (node (ref "C14") (pin "2") (pinfunction "2_2") (pintype "passive"))
      (node (ref "C15") (pin "2") (pinfunction "2_2") (pintype "passive"))
      (node (ref "C16") (pin "2") (pinfunction "2_2") (pintype "passive"))
      (node (ref "C17") (pin "-") (pinfunction "-_-") (pintype "passive"))
      (node (ref "C18") (pin "2") (pinfunction "2_2") (pintype "passive"))
      (node (ref "C19") (pin "2") (pinfunction "2_2") (pintype "passive"))
      (node (ref "C2") (pin "2") (pinfunction "2_2") (pintype "passive"))
      (node (ref "C20") (pin "-") (pinfunction "-_-") (pintype "passive"))
      (node (ref "C21") (pin "2") (pinfunction "2_2") (pintype "passive"))
      (node (ref "C22") (pin "2") (pinfunction "2_2") (pintype "passive"))
      (node (ref "C23") (pin "2") (pinfunction "2_2") (pintype "passive"))
      (node (ref "C24") (pin "1") (pinfunction "1_1") (pintype "passive"))
      (node (ref "C25") (pin "1") (pinfunction "1_1") (pintype "passive"))
      (node (ref "C3") (pin "2") (pinfunction "2_2") (pintype "passive"))
      (node (ref "C4") (pin "2") (pinfunction "2_2") (pintype "passive"))
      (node (ref "C5") (pin "2") (pinfunction "2_2") (pintype "passive"))
      (node (ref "C6") (pin "-") (pinfunction "-_-") (pintype "passive"))
      (node (ref "C7") (pin "-") (pinfunction "-_-") (pintype "passive"))
      (node (ref "J1") (pin "1") (pinfunction "1_1") (pintype "passive"))
      (node (ref "J10") (pin "1") (pinfunction "1_1") (pintype "passive"))
      (node (ref "J11") (pin "6") (pinfunction "6_6") (pintype "passive"))
      (node (ref "J12") (pin "1") (pinfunction "1_1") (pintype "passive"))
      (node (ref "R10") (pin "2") (pinfunction "2_2") (pintype "passive"))
      (node (ref "R11") (pin "1") (pinfunction "1_1") (pintype "passive"))
      (node (ref "R12") (pin "1") (pinfunction "1_1") (pintype "passive"))
      (node (ref "R14") (pin "1") (pinfunction "1_1") (pintype "passive"))
      (node (ref "R15") (pin "2") (pinfunction "2_2") (pintype "passive"))
      (node (ref "R16") (pin "2") (pinfunction "2_2") (pintype "passive"))
      (node (ref "R17") (pin "2") (pinfunction "2_2") (pintype "passive"))
      (node (ref "R2") (pin "2") (pinfunction "2_2") (pintype "passive"))
      (node (ref "R20") (pin "1") (pinfunction "1_1") (pintype "passive"))
      (node (ref "R21") (pin "1") (pinfunction "1_1") (pintype "passive"))
      (node (ref "R25") (pin "1") (pinfunction "1_1") (pintype "passive"))
      (node (ref "R3") (pin "2") (pinfunction "2_2") (pintype "passive"))
      (node (ref "R34") (pin "1") (pinfunction "1_1") (pintype "passive"))
      (node (ref "R4") (pin "2") (pinfunction "2_2") (pintype "passive"))
      (node (ref "R5") (pin "2") (pinfunction "2_2") (pintype "passive"))
      (node (ref "R6") (pin "2") (pinfunction "2_2") (pintype "passive"))
      (node (ref "R7") (pin "1") (pinfunction "1_1") (pintype "passive"))
      (node (ref "S3") (pin "1") (pinfunction "O_1") (pintype "passive"))
      (node (ref "TM1") (pin "1") (pinfunction "A_1") (pintype "passive"))
      (node (ref "TM2") (pin "1") (pinfunction "A_1") (pintype "passive"))
      (node (ref "U$1") (pin "12") (pinfunction "VSS_12") (pintype "power_in"))
      (node (ref "U$1") (pin "15") (pinfunction "INHIBIT_15") (pintype "passive"))
      (node (ref "U$3") (pin "2") (pinfunction "GND_2") (pintype "passive"))
      (node (ref "U1") (pin "9") (pinfunction "GND_9") (pintype "passive"))
      (node (ref "U10") (pin "1") (pinfunction "1_1") (pintype "passive"))
      (node (ref "U11") (pin "2") (pinfunction "SWITCHEMITTER_2") (pintype "passive"))
      (node (ref "U11") (pin "4") (pinfunction "GND_4") (pintype "power_in"))
      (node (ref "U11") (pin "9") (pinfunction "EPAD_9") (pintype "power_in"))
      (node (ref "U2") (pin "9") (pinfunction "GND_9") (pintype "passive"))
      (node (ref "U3") (pin "2") (pinfunction "COMMON_2") (pintype "power_in"))
      (node (ref "U3") (pin "4") (pinfunction "EPAD_4") (pintype "passive"))
      (node (ref "U4") (pin "21") (pinfunction "GND_21") (pintype "power_in"))
      (node (ref "U4") (pin "EPAD") (pinfunction "EPAD_EPAD") (pintype "passive"))
      (node (ref "U5") (pin "21") (pinfunction "GND_21") (pintype "power_in"))
      (node (ref "U5") (pin "EPAD") (pinfunction "EPAD_EPAD") (pintype "passive"))
      (node (ref "U6") (pin "GND") (pinfunction "GND_GND") (pintype "bidirectional"))
      (node (ref "U7") (pin "21") (pinfunction "AGND_21") (pintype "bidirectional"))
      (node (ref "U7") (pin "3") (pinfunction "GND_3") (pintype "bidirectional"))
      (node (ref "U7") (pin "5") (pinfunction "GND_5") (pintype "bidirectional"))
      (node (ref "U9") (pin "1") (pinfunction "1_1") (pintype "passive"))
      (node (ref "Y1") (pin "2") (pinfunction "2_2") (pintype "passive"))
    )
    (net (code "36") (name "MEGARX") (class "Default")
      (node (ref "Q2") (pin "3") (pinfunction "D_3") (pintype "passive"))
      (node (ref "R26") (pin "1") (pinfunction "1_1") (pintype "passive"))
      (node (ref "U7") (pin "30") (pinfunction "PD0(RXD)_30") (pintype "bidirectional"))
    )
    (net (code "37") (name "MEGARXLV") (class "Default")
      (node (ref "JP1") (pin "3") (pinfunction "3_3") (pintype "passive"))
      (node (ref "JP2") (pin "1") (pinfunction "1_1") (pintype "passive"))
      (node (ref "Q2") (pin "2") (pinfunction "S_2") (pintype "passive"))
      (node (ref "R27") (pin "1") (pinfunction "1_1") (pintype "passive"))
    )
    (net (code "38") (name "MEGATX") (class "Default")
      (node (ref "Q1") (pin "3") (pinfunction "D_3") (pintype "passive"))
      (node (ref "R23") (pin "1") (pinfunction "1_1") (pintype "passive"))
      (node (ref "U7") (pin "31") (pinfunction "PD1(TXD)_31") (pintype "bidirectional"))
    )
    (net (code "39") (name "MEGATXLV") (class "Default")
      (node (ref "JP1") (pin "1") (pinfunction "1_1") (pintype "passive"))
      (node (ref "JP2") (pin "3") (pinfunction "3_3") (pintype "passive"))
      (node (ref "Q1") (pin "2") (pinfunction "S_2") (pintype "passive"))
      (node (ref "R22") (pin "1") (pinfunction "1_1") (pintype "passive"))
    )
    (net (code "40") (name "Net-(20V!-Pad1)") (class "Default")
      (node (ref "20V!") (pin "1") (pinfunction "1_1") (pintype "passive"))
      (node (ref "C17") (pin "+") (pinfunction "+_+") (pintype "passive"))
      (node (ref "D2") (pin "C") (pinfunction "C_C") (pintype "passive"))
      (node (ref "R36") (pin "1") (pinfunction "1_1") (pintype "passive"))
    )
    (net (code "41") (name "Net-(D1-BLU)") (class "Default")
      (node (ref "D1") (pin "B") (pinfunction "BLU_B") (pintype "bidirectional"))
      (node (ref "R29") (pin "1") (pinfunction "1_1") (pintype "passive"))
    )
    (net (code "42") (name "Net-(D1-GRN)") (class "Default")
      (node (ref "D1") (pin "G") (pinfunction "GRN_G") (pintype "bidirectional"))
      (node (ref "R32") (pin "1") (pinfunction "1_1") (pintype "passive"))
    )
    (net (code "43") (name "Net-(D1-RED)") (class "Default")
      (node (ref "D1") (pin "R") (pinfunction "RED_R") (pintype "bidirectional"))
      (node (ref "R28") (pin "1") (pinfunction "1_1") (pintype "passive"))
    )
    (net (code "44") (name "Net-(J12-Pad3)") (class "Default")
      (node (ref "J12") (pin "3") (pinfunction "3_3") (pintype "passive"))
      (node (ref "U8") (pin "2") (pinfunction "2_2") (pintype "passive"))
    )
    (net (code "45") (name "Net-(L1-1)") (class "Default")
      (node (ref "L1") (pin "P$1") (pinfunction "1_P$1") (pintype "passive"))
      (node (ref "R33") (pin "2") (pinfunction "2_2") (pintype "passive"))
      (node (ref "R35") (pin "1") (pinfunction "1_1") (pintype "passive"))
      (node (ref "U11") (pin "7") (pinfunction "IPK_7") (pintype "passive"))
    )
    (net (code "46") (name "Net-(L1-2)") (class "Default")
      (node (ref "D2") (pin "A") (pinfunction "A_A") (pintype "passive"))
      (node (ref "L1") (pin "P$2") (pinfunction "2_P$2") (pintype "passive"))
      (node (ref "U11") (pin "1") (pinfunction "SWITCHCOLLECTOR_1") (pintype "passive"))
    )
    (net (code "47") (name "Net-(LED1-PadC)") (class "Default")
      (node (ref "LED1") (pin "C") (pinfunction "C_C") (pintype "passive"))
      (node (ref "R20") (pin "2") (pinfunction "2_2") (pintype "passive"))
    )
    (net (code "48") (name "Net-(LED2-PadC)") (class "Default")
      (node (ref "LED2") (pin "C") (pinfunction "C_C") (pintype "passive"))
      (node (ref "R7") (pin "2") (pinfunction "2_2") (pintype "passive"))
    )
    (net (code "49") (name "Net-(LED3-PadC)") (class "Default")
      (node (ref "LED3") (pin "C") (pinfunction "C_C") (pintype "passive"))
      (node (ref "R11") (pin "2") (pinfunction "2_2") (pintype "passive"))
    )
    (net (code "50") (name "Net-(LED4-PadC)") (class "Default")
      (node (ref "LED4") (pin "C") (pinfunction "C_C") (pintype "passive"))
      (node (ref "R12") (pin "2") (pinfunction "2_2") (pintype "passive"))
    )
    (net (code "51") (name "Net-(LED5-PadA)") (class "Default")
      (node (ref "LED5") (pin "A") (pinfunction "A_A") (pintype "passive"))
      (node (ref "U6") (pin "GPIO4") (pinfunction "GPIO4_GPIO4") (pintype "bidirectional"))
    )
    (net (code "52") (name "Net-(LED5-PadC)") (class "Default")
      (node (ref "LED5") (pin "C") (pinfunction "C_C") (pintype "passive"))
      (node (ref "R21") (pin "2") (pinfunction "2_2") (pintype "passive"))
    )
    (net (code "53") (name "Net-(LED6-PadC)") (class "Default")
      (node (ref "LED6") (pin "C") (pinfunction "C_C") (pintype "passive"))
      (node (ref "R25") (pin "2") (pinfunction "2_2") (pintype "passive"))
    )
    (net (code "54") (name "Net-(R14-Pad2)") (class "Default")
      (node (ref "R14") (pin "2") (pinfunction "2_2") (pintype "passive"))
      (node (ref "U6") (pin "GPIO15") (pinfunction "GPIO15_GPIO15") (pintype "bidirectional"))
    )
    (net (code "55") (name "Net-(R30-Pad1)") (class "Default")
      (node (ref "R30") (pin "1") (pinfunction "1_1") (pintype "passive"))
      (node (ref "U6") (pin "CH_PD") (pinfunction "CH_PD_CH_PD") (pintype "bidirectional"))
    )
    (net (code "56") (name "Net-(U$1-CHANNELIN{slash}OUT0)") (class "Default")
      (node (ref "U$1") (pin "9") (pinfunction "CHANNELIN/OUT0_9") (pintype "bidirectional"))
      (node (ref "U1") (pin "1") (pinfunction "1B_1") (pintype "passive"))
    )
    (net (code "57") (name "Net-(U$1-CHANNELIN{slash}OUT1)") (class "Default")
      (node (ref "U$1") (pin "8") (pinfunction "CHANNELIN/OUT1_8") (pintype "bidirectional"))
      (node (ref "U1") (pin "2") (pinfunction "2B_2") (pintype "passive"))
    )
    (net (code "58") (name "Net-(U$1-CHANNELIN{slash}OUT2)") (class "Default")
      (node (ref "U$1") (pin "7") (pinfunction "CHANNELIN/OUT2_7") (pintype "bidirectional"))
      (node (ref "U1") (pin "3") (pinfunction "3B_3") (pintype "passive"))
    )
    (net (code "59") (name "Net-(U$1-CHANNELIN{slash}OUT3)") (class "Default")
      (node (ref "U$1") (pin "6") (pinfunction "CHANNELIN/OUT3_6") (pintype "bidirectional"))
      (node (ref "U1") (pin "4") (pinfunction "4B_4") (pintype "passive"))
    )
    (net (code "60") (name "Net-(U$1-CHANNELIN{slash}OUT4)") (class "Default")
      (node (ref "U$1") (pin "5") (pinfunction "CHANNELIN/OUT4_5") (pintype "bidirectional"))
      (node (ref "U1") (pin "5") (pinfunction "5B_5") (pintype "passive"))
    )
    (net (code "61") (name "Net-(U$1-CHANNELIN{slash}OUT5)") (class "Default")
      (node (ref "U$1") (pin "4") (pinfunction "CHANNELIN/OUT5_4") (pintype "bidirectional"))
      (node (ref "U1") (pin "6") (pinfunction "6B_6") (pintype "passive"))
    )
    (net (code "62") (name "Net-(U$1-CHANNELIN{slash}OUT6)") (class "Default")
      (node (ref "U$1") (pin "3") (pinfunction "CHANNELIN/OUT6_3") (pintype "bidirectional"))
      (node (ref "U1") (pin "7") (pinfunction "7B_7") (pintype "passive"))
    )
    (net (code "63") (name "Net-(U$1-CHANNELIN{slash}OUT7)") (class "Default")
      (node (ref "U$1") (pin "2") (pinfunction "CHANNELIN/OUT7_2") (pintype "bidirectional"))
      (node (ref "U1") (pin "8") (pinfunction "8B_8") (pintype "passive"))
    )
    (net (code "64") (name "Net-(U$1-CHANNELIN{slash}OUT8)") (class "Default")
      (node (ref "U$1") (pin "23") (pinfunction "CHANNELIN/OUT8_23") (pintype "bidirectional"))
      (node (ref "U2") (pin "1") (pinfunction "1B_1") (pintype "passive"))
    )
    (net (code "65") (name "Net-(U$1-CHANNELIN{slash}OUT9)") (class "Default")
      (node (ref "U$1") (pin "22") (pinfunction "CHANNELIN/OUT9_22") (pintype "bidirectional"))
      (node (ref "U2") (pin "2") (pinfunction "2B_2") (pintype "passive"))
    )
    (net (code "66") (name "Net-(U$1-CHANNELIN{slash}OUT10)") (class "Default")
      (node (ref "U$1") (pin "21") (pinfunction "CHANNELIN/OUT10_21") (pintype "bidirectional"))
      (node (ref "U2") (pin "3") (pinfunction "3B_3") (pintype "passive"))
    )
    (net (code "67") (name "Net-(U$1-CHANNELIN{slash}OUT11)") (class "Default")
      (node (ref "U$1") (pin "20") (pinfunction "CHANNELIN/OUT11_20") (pintype "bidirectional"))
      (node (ref "U2") (pin "4") (pinfunction "4B_4") (pintype "passive"))
    )
    (net (code "68") (name "Net-(U$1-CHANNELIN{slash}OUT12)") (class "Default")
      (node (ref "U$1") (pin "19") (pinfunction "CHANNELIN/OUT12_19") (pintype "bidirectional"))
      (node (ref "U2") (pin "5") (pinfunction "5B_5") (pintype "passive"))
    )
    (net (code "69") (name "Net-(U$1-CHANNELIN{slash}OUT13)") (class "Default")
      (node (ref "U$1") (pin "18") (pinfunction "CHANNELIN/OUT13_18") (pintype "bidirectional"))
      (node (ref "U2") (pin "6") (pinfunction "6B_6") (pintype "passive"))
    )
    (net (code "70") (name "Net-(U$1-CHANNELIN{slash}OUT14)") (class "Default")
      (node (ref "U$1") (pin "17") (pinfunction "CHANNELIN/OUT14_17") (pintype "bidirectional"))
      (node (ref "U2") (pin "7") (pinfunction "7B_7") (pintype "passive"))
    )
    (net (code "71") (name "Net-(U$1-CHANNELIN{slash}OUT15)") (class "Default")
      (node (ref "U$1") (pin "16") (pinfunction "CHANNELIN/OUT15_16") (pintype "bidirectional"))
      (node (ref "U2") (pin "8") (pinfunction "8B_8") (pintype "passive"))
    )
    (net (code "72") (name "Net-(U$3-BYP)") (class "Default")
      (node (ref "C2") (pin "1") (pinfunction "1_1") (pintype "passive"))
      (node (ref "U$3") (pin "4") (pinfunction "BYP_4") (pintype "passive"))
    )
    (net (code "73") (name "Net-(U$3-~{SHDN})") (class "Default")
      (node (ref "R1") (pin "1") (pinfunction "1_1") (pintype "passive"))
      (node (ref "U$3") (pin "3") (pinfunction "~{SHDN}_3") (pintype "passive"))
    )
    (net (code "74") (name "Net-(U1-1C)") (class "Default")
      (node (ref "U1") (pin "18") (pinfunction "1C_18") (pintype "passive"))
      (node (ref "X1") (pin "8") (pinfunction "1_8") (pintype "passive"))
    )
    (net (code "75") (name "Net-(U1-2C)") (class "Default")
      (node (ref "U1") (pin "17") (pinfunction "2C_17") (pintype "passive"))
      (node (ref "X1") (pin "7") (pinfunction "1_7") (pintype "passive"))
    )
    (net (code "76") (name "Net-(U1-3C)") (class "Default")
      (node (ref "U1") (pin "16") (pinfunction "3C_16") (pintype "passive"))
      (node (ref "X1") (pin "4") (pinfunction "1_4") (pintype "passive"))
    )
    (net (code "77") (name "Net-(U1-4C)") (class "Default")
      (node (ref "U1") (pin "15") (pinfunction "4C_15") (pintype "passive"))
      (node (ref "X1") (pin "5") (pinfunction "1_5") (pintype "passive"))
    )
    (net (code "78") (name "Net-(U1-5C)") (class "Default")
      (node (ref "U1") (pin "14") (pinfunction "5C_14") (pintype "passive"))
      (node (ref "X1") (pin "6") (pinfunction "1_6") (pintype "passive"))
    )
    (net (code "79") (name "Net-(U1-6C)") (class "Default")
      (node (ref "U1") (pin "13") (pinfunction "6C_13") (pintype "passive"))
      (node (ref "X1") (pin "13") (pinfunction "1_13") (pintype "passive"))
    )
    (net (code "80") (name "Net-(U1-7C)") (class "Default")
      (node (ref "U1") (pin "12") (pinfunction "7C_12") (pintype "passive"))
      (node (ref "X1") (pin "14") (pinfunction "1_14") (pintype "passive"))
    )
    (net (code "81") (name "Net-(U1-8C)") (class "Default")
      (node (ref "U1") (pin "11") (pinfunction "8C_11") (pintype "passive"))
      (node (ref "X1") (pin "15") (pinfunction "1_15") (pintype "passive"))
    )
    (net (code "82") (name "Net-(U2-1C)") (class "Default")
      (node (ref "U2") (pin "18") (pinfunction "1C_18") (pintype "passive"))
      (node (ref "X1") (pin "12") (pinfunction "1_12") (pintype "passive"))
    )
    (net (code "83") (name "Net-(U2-2C)") (class "Default")
      (node (ref "U2") (pin "17") (pinfunction "2C_17") (pintype "passive"))
      (node (ref "X1") (pin "11") (pinfunction "1_11") (pintype "passive"))
    )
    (net (code "84") (name "Net-(U2-3C)") (class "Default")
      (node (ref "U2") (pin "16") (pinfunction "3C_16") (pintype "passive"))
      (node (ref "X1") (pin "10") (pinfunction "1_10") (pintype "passive"))
    )
    (net (code "85") (name "Net-(U2-4C)") (class "Default")
      (node (ref "U2") (pin "15") (pinfunction "4C_15") (pintype "passive"))
      (node (ref "X1") (pin "9") (pinfunction "1_9") (pintype "passive"))
    )
    (net (code "86") (name "Net-(U4-ADECAY)") (class "Default")
      (node (ref "R10") (pin "1") (pinfunction "1_1") (pintype "passive"))
      (node (ref "U4") (pin "3") (pinfunction "ADECAY_3") (pintype "input"))
    )
    (net (code "87") (name "Net-(U4-AISEN)") (class "Default")
      (node (ref "R16") (pin "1") (pinfunction "1_1") (pintype "passive"))
      (node (ref "U4") (pin "5") (pinfunction "AISEN_5") (pintype "bidirectional"))
    )
    (net (code "88") (name "Net-(U4-AOUT1)") (class "Default")
      (node (ref "J3") (pin "4") (pinfunction "4_4") (pintype "passive"))
      (node (ref "J4") (pin "4") (pinfunction "4_4") (pintype "passive"))
      (node (ref "U4") (pin "4") (pinfunction "AOUT1_4") (pintype "output"))
    )
    (net (code "89") (name "Net-(U4-AOUT2)") (class "Default")
      (node (ref "J3") (pin "3") (pinfunction "3_3") (pintype "passive"))
      (node (ref "J4") (pin "3") (pinfunction "3_3") (pintype "passive"))
      (node (ref "U4") (pin "6") (pinfunction "AOUT2_6") (pintype "output"))
    )
    (net (code "90") (name "Net-(U4-BDECAY)") (class "Default")
      (node (ref "R17") (pin "1") (pinfunction "1_1") (pintype "passive"))
      (node (ref "U4") (pin "2") (pinfunction "BDECAY_2") (pintype "input"))
    )
    (net (code "91") (name "Net-(U4-BISEN)") (class "Default")
      (node (ref "R15") (pin "1") (pinfunction "1_1") (pintype "passive"))
      (node (ref "U4") (pin "8") (pinfunction "BISEN_8") (pintype "bidirectional"))
    )
    (net (code "92") (name "Net-(U4-BOUT1)") (class "Default")
      (node (ref "J3") (pin "2") (pinfunction "2_2") (pintype "passive"))
      (node (ref "J4") (pin "1") (pinfunction "1_1") (pintype "passive"))
      (node (ref "U4") (pin "9") (pinfunction "BOUT1_9") (pintype "output"))
    )
    (net (code "93") (name "Net-(U4-BOUT2)") (class "Default")
      (node (ref "J3") (pin "1") (pinfunction "1_1") (pintype "passive"))
      (node (ref "J4") (pin "2") (pinfunction "2_2") (pintype "passive"))
      (node (ref "U4") (pin "7") (pinfunction "BOUT2_7") (pintype "output"))
    )
    (net (code "94") (name "Net-(U4-M0{slash}APHASE)") (class "Default")
      (node (ref "M02") (pin "1") (pinfunction "1_1") (pintype "passive"))
      (node (ref "U4") (pin "13") (pinfunction "M0/APHASE_13") (pintype "input"))
    )
    (net (code "95") (name "Net-(U4-M1)") (class "Default")
      (node (ref "M12") (pin "1") (pinfunction "1_1") (pintype "passive"))
      (node (ref "U4") (pin "14") (pinfunction "M1_14") (pintype "input"))
    )
    (net (code "96") (name "Net-(U4-NFAULT)") (class "Default")
      (node (ref "R18") (pin "1") (pinfunction "1_1") (pintype "passive"))
      (node (ref "U4") (pin "16") (pinfunction "NFAULT_16") (pintype "output"))
    )
    (net (code "97") (name "Net-(U4-NSLEEP)") (class "Default")
      (node (ref "R19") (pin "1") (pinfunction "1_1") (pintype "passive"))
      (node (ref "U4") (pin "1") (pinfunction "NSLEEP_1") (pintype "input"))
    )
    (net (code "98") (name "Net-(U4-VCP)") (class "Default")
      (node (ref "C9") (pin "1") (pinfunction "1_1") (pintype "passive"))
      (node (ref "U4") (pin "17") (pinfunction "VCP_17") (pintype "output"))
    )
    (net (code "99") (name "Net-(U5-ADECAY)") (class "Default")
      (node (ref "R2") (pin "1") (pinfunction "1_1") (pintype "passive"))
      (node (ref "U5") (pin "3") (pinfunction "ADECAY_3") (pintype "input"))
    )
    (net (code "100") (name "Net-(U5-AISEN)") (class "Default")
      (node (ref "R4") (pin "1") (pinfunction "1_1") (pintype "passive"))
      (node (ref "U5") (pin "5") (pinfunction "AISEN_5") (pintype "bidirectional"))
    )
    (net (code "101") (name "Net-(U5-AOUT1)") (class "Default")
      (node (ref "J2") (pin "4") (pinfunction "4_4") (pintype "passive"))
      (node (ref "J5") (pin "4") (pinfunction "4_4") (pintype "passive"))
      (node (ref "U5") (pin "4") (pinfunction "AOUT1_4") (pintype "output"))
    )
    (net (code "102") (name "Net-(U5-AOUT2)") (class "Default")
      (node (ref "J2") (pin "3") (pinfunction "3_3") (pintype "passive"))
      (node (ref "J5") (pin "3") (pinfunction "3_3") (pintype "passive"))
      (node (ref "U5") (pin "6") (pinfunction "AOUT2_6") (pintype "output"))
    )
    (net (code "103") (name "Net-(U5-BDECAY)") (class "Default")
      (node (ref "R5") (pin "1") (pinfunction "1_1") (pintype "passive"))
      (node (ref "U5") (pin "2") (pinfunction "BDECAY_2") (pintype "input"))
    )
    (net (code "104") (name "Net-(U5-BISEN)") (class "Default")
      (node (ref "R3") (pin "1") (pinfunction "1_1") (pintype "passive"))
      (node (ref "U5") (pin "8") (pinfunction "BISEN_8") (pintype "bidirectional"))
    )
    (net (code "105") (name "Net-(U5-BOUT1)") (class "Default")
      (node (ref "J2") (pin "2") (pinfunction "2_2") (pintype "passive"))
      (node (ref "J5") (pin "1") (pinfunction "1_1") (pintype "passive"))
      (node (ref "U5") (pin "9") (pinfunction "BOUT1_9") (pintype "output"))
    )
    (net (code "106") (name "Net-(U5-BOUT2)") (class "Default")
      (node (ref "J2") (pin "1") (pinfunction "1_1") (pintype "passive"))
      (node (ref "J5") (pin "2") (pinfunction "2_2") (pintype "passive"))
      (node (ref "U5") (pin "7") (pinfunction "BOUT2_7") (pintype "output"))
    )
    (net (code "107") (name "Net-(U5-M0{slash}APHASE)") (class "Default")
      (node (ref "M01") (pin "1") (pinfunction "1_1") (pintype "passive"))
      (node (ref "U5") (pin "13") (pinfunction "M0/APHASE_13") (pintype "input"))
    )
    (net (code "108") (name "Net-(U5-M1)") (class "Default")
      (node (ref "M11") (pin "1") (pinfunction "1_1") (pintype "passive"))
      (node (ref "U5") (pin "14") (pinfunction "M1_14") (pintype "input"))
    )
    (net (code "109") (name "Net-(U5-NFAULT)") (class "Default")
      (node (ref "R8") (pin "1") (pinfunction "1_1") (pintype "passive"))
      (node (ref "U5") (pin "16") (pinfunction "NFAULT_16") (pintype "output"))
    )
    (net (code "110") (name "Net-(U5-NSLEEP)") (class "Default")
      (node (ref "R9") (pin "1") (pinfunction "1_1") (pintype "passive"))
      (node (ref "U5") (pin "1") (pinfunction "NSLEEP_1") (pintype "input"))
    )
    (net (code "111") (name "Net-(U5-VCP)") (class "Default")
      (node (ref "C11") (pin "1") (pinfunction "1_1") (pintype "passive"))
      (node (ref "U5") (pin "17") (pinfunction "VCP_17") (pintype "output"))
    )
    (net (code "112") (name "Net-(U7-PB6(XTAL1{slash}TOSC1))") (class "Default")
      (node (ref "U7") (pin "7") (pinfunction "PB6(XTAL1/TOSC1)_7") (pintype "bidirectional"))
      (node (ref "Y1") (pin "1") (pinfunction "1_1") (pintype "passive"))
    )
    (net (code "113") (name "Net-(U7-PB7(XTAL2{slash}TOSC2))") (class "Default")
      (node (ref "U7") (pin "8") (pinfunction "PB7(XTAL2/TOSC2)_8") (pintype "bidirectional"))
      (node (ref "Y1") (pin "3") (pinfunction "3_3") (pintype "passive"))
    )
    (net (code "114") (name "Net-(U7-PD7(AIN1))") (class "Default")
      (node (ref "LED6") (pin "A") (pinfunction "A_A") (pintype "passive"))
      (node (ref "U7") (pin "11") (pinfunction "PD7(AIN1)_11") (pintype "bidirectional"))
    )
    (net (code "115") (name "Net-(U11-COMPARATORINVERTINGINPUT)") (class "Default")
      (node (ref "R34") (pin "2") (pinfunction "2_2") (pintype "passive"))
      (node (ref "R36") (pin "2") (pinfunction "2_2") (pintype "passive"))
      (node (ref "U11") (pin "5") (pinfunction "COMPARATORINVERTINGINPUT_5") (pintype "passive"))
    )
    (net (code "116") (name "Net-(U11-DRIVERCOLLECTOR)") (class "Default")
      (node (ref "R33") (pin "1") (pinfunction "1_1") (pintype "passive"))
      (node (ref "U11") (pin "8") (pinfunction "DRIVERCOLLECTOR_8") (pintype "passive"))
    )
    (net (code "117") (name "Net-(U11-TIMINGCAPACITOR)") (class "Default")
      (node (ref "C25") (pin "2") (pinfunction "2_2") (pintype "passive"))
      (node (ref "U11") (pin "3") (pinfunction "TIMINGCAPACITOR_3") (pintype "passive"))
    )
    (net (code "118") (name "REF1") (class "Default")
      (node (ref "TM1") (pin "2") (pinfunction "S_2") (pintype "passive"))
      (node (ref "U4") (pin "22") (pinfunction "AVREF_22") (pintype "input"))
      (node (ref "U4") (pin "23") (pinfunction "BVREF_23") (pintype "input"))
    )
    (net (code "119") (name "REF2") (class "Default")
      (node (ref "TM2") (pin "2") (pinfunction "S_2") (pintype "passive"))
      (node (ref "U5") (pin "22") (pinfunction "AVREF_22") (pintype "input"))
      (node (ref "U5") (pin "23") (pinfunction "BVREF_23") (pintype "input"))
    )
    (net (code "120") (name "VCC") (class "Default")
      (node (ref "C20") (pin "+") (pinfunction "+_+") (pintype "passive"))
      (node (ref "C21") (pin "1") (pinfunction "1_1") (pintype "passive"))
      (node (ref "C22") (pin "1") (pinfunction "1_1") (pintype "passive"))
      (node (ref "C23") (pin "1") (pinfunction "1_1") (pintype "passive"))
      (node (ref "C24") (pin "2") (pinfunction "2_2") (pintype "passive"))
      (node (ref "C5") (pin "1") (pinfunction "1_1") (pintype "passive"))
      (node (ref "R35") (pin "2") (pinfunction "2_2") (pintype "passive"))
      (node (ref "U11") (pin "6") (pinfunction "VCC_6") (pintype "power_in"))
      (node (ref "U3") (pin "1") (pinfunction "INPUT_1") (pintype "input"))
      (node (ref "U8") (pin "1") (pinfunction "1_1") (pintype "passive"))
    )
    (net (code "121") (name "unconnected-(J10-Pad2)") (class "Default")
      (node (ref "J10") (pin "2") (pinfunction "2_2") (pintype "passive"))
    )
    (net (code "122") (name "unconnected-(J12-Pad2)") (class "Default")
      (node (ref "J12") (pin "2") (pinfunction "2_2") (pintype "passive"))
    )
    (net (code "123") (name "unconnected-(U2-5C-Pad14)") (class "Default")
      (node (ref "U2") (pin "14") (pinfunction "5C_14") (pintype "passive"))
    )
    (net (code "124") (name "unconnected-(U2-6C-Pad13)") (class "Default")
      (node (ref "U2") (pin "13") (pinfunction "6C_13") (pintype "passive"))
    )
    (net (code "125") (name "unconnected-(U2-7C-Pad12)") (class "Default")
      (node (ref "U2") (pin "12") (pinfunction "7C_12") (pintype "passive"))
    )
    (net (code "126") (name "unconnected-(U2-8C-Pad11)") (class "Default")
      (node (ref "U2") (pin "11") (pinfunction "8C_11") (pintype "passive"))
    )
    (net (code "127") (name "unconnected-(U6-*GPIO9-PadGPIO9)") (class "Default")
      (node (ref "U6") (pin "GPIO9") (pinfunction "*GPIO9_GPIO9") (pintype "bidirectional"))
    )
    (net (code "128") (name "unconnected-(U6-*GPIO10-PadGPIO10)") (class "Default")
      (node (ref "U6") (pin "GPIO10") (pinfunction "*GPIO10_GPIO10") (pintype "bidirectional"))
    )
    (net (code "129") (name "unconnected-(U6-PadADC)") (class "Default")
      (node (ref "U6") (pin "ADC") (pinfunction "ADC_ADC") (pintype "bidirectional"))
    )
    (net (code "130") (name "unconnected-(U6-PadCS0)") (class "Default")
      (node (ref "U6") (pin "CS0") (pinfunction "CS0_CS0") (pintype "bidirectional"))
    )
    (net (code "131") (name "unconnected-(U6-PadGPIO5)") (class "Default")
      (node (ref "U6") (pin "GPIO5") (pinfunction "GPIO5_GPIO5") (pintype "bidirectional"))
    )
    (net (code "132") (name "unconnected-(U6-PadMISO)") (class "Default")
      (node (ref "U6") (pin "MISO") (pinfunction "MISO_MISO") (pintype "bidirectional"))
    )
    (net (code "133") (name "unconnected-(U6-PadMOSI)") (class "Default")
      (node (ref "U6") (pin "MOSI") (pinfunction "MOSI_MOSI") (pintype "bidirectional"))
    )
    (net (code "134") (name "unconnected-(U6-PadSCLK)") (class "Default")
      (node (ref "U6") (pin "SCLK") (pinfunction "SCLK_SCLK") (pintype "bidirectional"))
    )
    (net (code "135") (name "unconnected-(U7-ADC6-Pad19)") (class "Default")
      (node (ref "U7") (pin "19") (pinfunction "ADC6_19") (pintype "bidirectional"))
    )
    (net (code "136") (name "unconnected-(U7-ADC7-Pad22)") (class "Default")
      (node (ref "U7") (pin "22") (pinfunction "ADC7_22") (pintype "bidirectional"))
    )
    (net (code "137") (name "unconnected-(U7-AREF-Pad20)") (class "Default")
      (node (ref "U7") (pin "20") (pinfunction "AREF_20") (pintype "bidirectional"))
    )
    (net (code "138") (name "unconnected-(U7-PC4(ADC4{slash}SDA)-Pad27)") (class "Default")
      (node (ref "U7") (pin "27") (pinfunction "PC4(ADC4/SDA)_27") (pintype "bidirectional"))
    )
    (net (code "139") (name "unconnected-(U7-PC5(ADC5{slash}SCL)-Pad28)") (class "Default")
      (node (ref "U7") (pin "28") (pinfunction "PC5(ADC5/SCL)_28") (pintype "bidirectional"))
    )
    (net (code "140") (name "unconnected-(U8-Pad3)") (class "Default")
      (node (ref "U8") (pin "3") (pinfunction "3_3") (pintype "passive"))
    )
    (net (code "141") (name "unconnected-(X1-Pad1)") (class "Default")
      (node (ref "X1") (pin "1") (pinfunction "1_1") (pintype "passive"))
    )
    (net (code "142") (name "unconnected-(X1I-1-Pad2)") (class "Default")
      (node (ref "X1") (pin "2") (pinfunction "1_2") (pintype "passive"))
    )
  )
)
